# Sheet1.net
KiCad netlist of a schematic drawn in Altium Designer
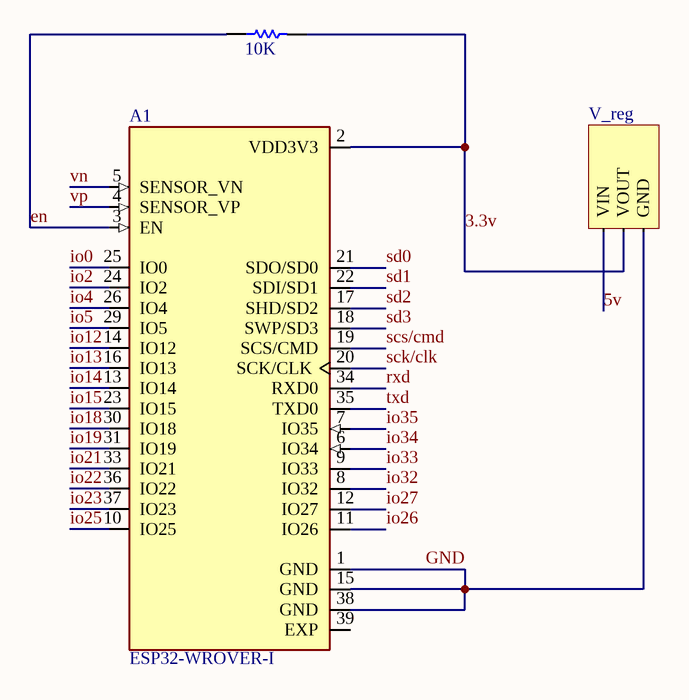
[diagram p0: Sheet1.SchDoc]

(export (version "E")
  (design (tool "Eeschema 10.0.6"))
  (components
    (comp (ref "A1")
      (value "ESP32-WROVER-I")
      (footprint "XCVR_ESP32-WROVER-I")
      (description "Module: combo; GPIO, I2C x2, I2S x2, SDIO, SPI x3, UART x3; U.FL")
      (libsource (lib "ESP32-WROVER-I") (part "ESP32-WROVER-I"))
    )
    (comp (ref "R1")
      (value "10K")
      (footprint "AXIAL-0.3")
      (description "Resistor")
      (fields (field (name "Comment") "Res1") (field (name "PUBLISHER") "Altium Limited"))
      (libsource (lib "Miscellaneous Devices") (part "Res1"))
    )
    (comp (ref "V_reg")
      (value "AMS1117 Breakout Board")
      (footprint "AMS1117 Breakout Board")
      (libsource (lib "AMS1117 Breakout Board") (part "AMS1117 Breakout Board"))
    )
  )
  (nets
    (net (code "1") (name "/3.3v") (class "Default")
      (node (ref "A1") (pin "2") (pinfunction "VDD3V3_2") (pintype "power_in"))
      (node (ref "R1") (pin "2") (pinfunction "2_2") (pintype "passive"))
      (node (ref "V_reg") (pin "VOUT") (pinfunction "VOUT_VOUT") (pintype "power_in"))
    )
    (net (code "2") (name "/5v") (class "Default")
      (node (ref "V_reg") (pin "VIN") (pinfunction "VIN_VIN") (pintype "power_in"))
    )
    (net (code "3") (name "/GND") (class "Default")
      (node (ref "A1") (pin "1") (pinfunction "GND_1") (pintype "power_in"))
      (node (ref "A1") (pin "15") (pinfunction "GND_15") (pintype "power_in"))
      (node (ref "A1") (pin "38") (pinfunction "GND_38") (pintype "power_in"))
      (node (ref "V_reg") (pin "GND") (pinfunction "GND_GND") (pintype "power_in"))
    )
    (net (code "4") (name "/en") (class "Default")
      (node (ref "A1") (pin "3") (pinfunction "EN_3") (pintype "input"))
      (node (ref "R1") (pin "1") (pinfunction "1_1") (pintype "passive"))
    )
    (net (code "5") (name "/io0") (class "Default")
      (node (ref "A1") (pin "25") (pinfunction "IO0_25") (pintype "bidirectional"))
    )
    (net (code "6") (name "/io2") (class "Default")
      (node (ref "A1") (pin "24") (pinfunction "IO2_24") (pintype "bidirectional"))
    )
    (net (code "7") (name "/io4") (class "Default")
      (node (ref "A1") (pin "26") (pinfunction "IO4_26") (pintype "bidirectional"))
    )
    (net (code "8") (name "/io5") (class "Default")
      (node (ref "A1") (pin "29") (pinfunction "IO5_29") (pintype "bidirectional"))
    )
    (net (code "9") (name "/io12") (class "Default")
      (node (ref "A1") (pin "14") (pinfunction "IO12_14") (pintype "bidirectional"))
    )
    (net (code "10") (name "/io13") (class "Default")
      (node (ref "A1") (pin "16") (pinfunction "IO13_16") (pintype "bidirectional"))
    )
    (net (code "11") (name "/io14") (class "Default")
      (node (ref "A1") (pin "13") (pinfunction "IO14_13") (pintype "bidirectional"))
    )
    (net (code "12") (name "/io15") (class "Default")
      (node (ref "A1") (pin "23") (pinfunction "IO15_23") (pintype "bidirectional"))
    )
    (net (code "13") (name "/io18") (class "Default")
      (node (ref "A1") (pin "30") (pinfunction "IO18_30") (pintype "bidirectional"))
    )
    (net (code "14") (name "/io19") (class "Default")
      (node (ref "A1") (pin "31") (pinfunction "IO19_31") (pintype "bidirectional"))
    )
    (net (code "15") (name "/io21") (class "Default")
      (node (ref "A1") (pin "33") (pinfunction "IO21_33") (pintype "bidirectional"))
    )
    (net (code "16") (name "/io22") (class "Default")
      (node (ref "A1") (pin "36") (pinfunction "IO22_36") (pintype "bidirectional"))
    )
    (net (code "17") (name "/io23") (class "Default")
      (node (ref "A1") (pin "37") (pinfunction "IO23_37") (pintype "bidirectional"))
    )
    (net (code "18") (name "/io25") (class "Default")
      (node (ref "A1") (pin "10") (pinfunction "IO25_10") (pintype "bidirectional"))
    )
    (net (code "19") (name "/io26") (class "Default")
      (node (ref "A1") (pin "11") (pinfunction "IO26_11") (pintype "bidirectional"))
    )
    (net (code "20") (name "/io27") (class "Default")
      (node (ref "A1") (pin "12") (pinfunction "IO27_12") (pintype "bidirectional"))
    )
    (net (code "21") (name "/io32") (class "Default")
      (node (ref "A1") (pin "8") (pinfunction "IO32_8") (pintype "bidirectional"))
    )
    (net (code "22") (name "/io33") (class "Default")
      (node (ref "A1") (pin "9") (pinfunction "IO33_9") (pintype "bidirectional"))
    )
    (net (code "23") (name "/io34") (class "Default")
      (node (ref "A1") (pin "6") (pinfunction "IO34_6") (pintype "input"))
    )
    (net (code "24") (name "/io35") (class "Default")
      (node (ref "A1") (pin "7") (pinfunction "IO35_7") (pintype "input"))
    )
    (net (code "25") (name "/rxd") (class "Default")
      (node (ref "A1") (pin "34") (pinfunction "RXD0_34") (pintype "bidirectional"))
    )
    (net (code "26") (name "/sck{slash}clk") (class "Default")
      (node (ref "A1") (pin "20") (pinfunction "SCK/CLK_20") (pintype "bidirectional"))
    )
    (net (code "27") (name "/scs{slash}cmd") (class "Default")
      (node (ref "A1") (pin "19") (pinfunction "SCS/CMD_19") (pintype "bidirectional"))
    )
    (net (code "28") (name "/sd0") (class "Default")
      (node (ref "A1") (pin "21") (pinfunction "SDO/SD0_21") (pintype "bidirectional"))
    )
    (net (code "29") (name "/sd1") (class "Default")
      (node (ref "A1") (pin "22") (pinfunction "SDI/SD1_22") (pintype "bidirectional"))
    )
    (net (code "30") (name "/sd2") (class "Default")
      (node (ref "A1") (pin "17") (pinfunction "SHD/SD2_17") (pintype "bidirectional"))
    )
    (net (code "31") (name "/sd3") (class "Default")
      (node (ref "A1") (pin "18") (pinfunction "SWP/SD3_18") (pintype "bidirectional"))
    )
    (net (code "32") (name "/txd") (class "Default")
      (node (ref "A1") (pin "35") (pinfunction "TXD0_35") (pintype "bidirectional"))
    )
    (net (code "33") (name "/vn") (class "Default")
      (node (ref "A1") (pin "5") (pinfunction "SENSOR_VN_5") (pintype "input"))
    )
    (net (code "34") (name "/vp") (class "Default")
      (node (ref "A1") (pin "4") (pinfunction "SENSOR_VP_4") (pintype "input"))
    )
    (net (code "35") (name "unconnected-(A1-EXP-Pad39)") (class "Default")
      (node (ref "A1") (pin "39") (pinfunction "EXP_39") (pintype "power_in"))
    )
  )
)
